# LightSensors_Buttons_LCD.net
KiCad netlist of a schematic drawn in Altium Designer
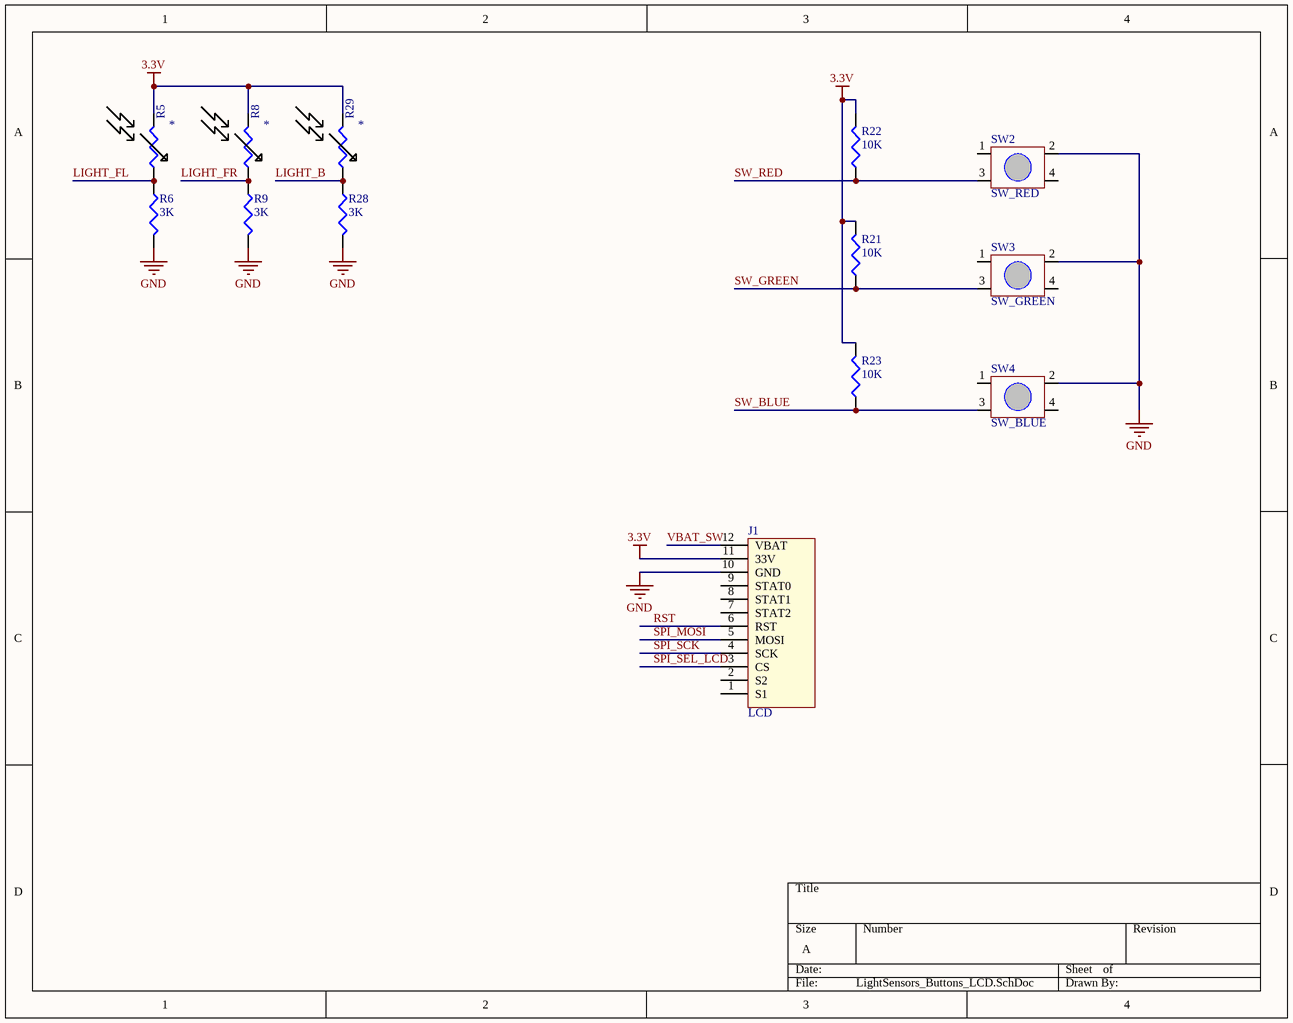
[diagram p0: LightSensors_Buttons_LCD.SchDoc]

(export (version "E")
  (design (tool "Eeschema 10.0.6"))
  (components
    (comp (ref "J1")
      (value "LCD")
      (footprint "LCD-6100breakout")
      (libsource (lib "mrone") (part "LCD-NokiaBreakout"))
    )
    (comp (ref "R5")
      (value "photoresistor")
      (footprint "photoresistor")
      (fields (field (name "ALTIUM_VALUE") "*"))
      (libsource (lib "mrone") (part "photoresistor"))
    )
    (comp (ref "R6")
      (value "3K")
      (footprint "RESC1608L")
      (description "Resistor")
      (fields (field (name "Comment") "Res3") (field (name "PUBLISHER") "Altium Limited"))
      (libsource (lib "Miscellaneous Devices") (part "Res3"))
    )
    (comp (ref "R8")
      (value "photoresistor")
      (footprint "photoresistor")
      (fields (field (name "ALTIUM_VALUE") "*"))
      (libsource (lib "mrone") (part "photoresistor"))
    )
    (comp (ref "R9")
      (value "3K")
      (footprint "RESC1608L")
      (description "Resistor")
      (fields (field (name "Comment") "Res3") (field (name "PUBLISHER") "Altium Limited"))
      (libsource (lib "Miscellaneous Devices") (part "Res3"))
    )
    (comp (ref "R21")
      (value "10K")
      (footprint "RESC1608L")
      (description "Resistor")
      (fields (field (name "Comment") "Res3") (field (name "PUBLISHER") "Altium Limited"))
      (libsource (lib "Miscellaneous Devices") (part "Res3"))
    )
    (comp (ref "R22")
      (value "10K")
      (footprint "RESC1608L")
      (description "Resistor")
      (fields (field (name "Comment") "Res3") (field (name "PUBLISHER") "Altium Limited"))
      (libsource (lib "Miscellaneous Devices") (part "Res3"))
    )
    (comp (ref "R23")
      (value "10K")
      (footprint "RESC1608L")
      (description "Resistor")
      (fields (field (name "Comment") "Res3") (field (name "PUBLISHER") "Altium Limited"))
      (libsource (lib "Miscellaneous Devices") (part "Res3"))
    )
    (comp (ref "R28")
      (value "3K")
      (footprint "RESC1608L")
      (description "Resistor")
      (fields (field (name "Comment") "Res3") (field (name "PUBLISHER") "Altium Limited"))
      (libsource (lib "Miscellaneous Devices") (part "Res3"))
    )
    (comp (ref "R29")
      (value "photoresistor")
      (footprint "photoresistor")
      (fields (field (name "ALTIUM_VALUE") "*"))
      (libsource (lib "mrone") (part "photoresistor"))
    )
    (comp (ref "SW2")
      (value "SW_RED")
      (footprint "SwitchTall-TL330")
      (libsource (lib "mrone") (part "Switch-TL330"))
    )
    (comp (ref "SW3")
      (value "SW_GREEN")
      (footprint "SwitchTall-TL330")
      (libsource (lib "mrone") (part "Switch-TL330"))
    )
    (comp (ref "SW4")
      (value "SW_BLUE")
      (footprint "SwitchTall-TL330")
      (libsource (lib "mrone") (part "Switch-TL330"))
    )
  )
  (nets
    (net (code "1") (name "/LIGHT_B") (class "Default")
      (node (ref "R28") (pin "1") (pinfunction "1_1") (pintype "passive"))
      (node (ref "R29") (pin "1") (pinfunction "1_1") (pintype "passive"))
    )
    (net (code "2") (name "/LIGHT_FL") (class "Default")
      (node (ref "R5") (pin "1") (pinfunction "1_1") (pintype "passive"))
      (node (ref "R6") (pin "1") (pinfunction "1_1") (pintype "passive"))
    )
    (net (code "3") (name "/LIGHT_FR") (class "Default")
      (node (ref "R8") (pin "1") (pinfunction "1_1") (pintype "passive"))
      (node (ref "R9") (pin "1") (pinfunction "1_1") (pintype "passive"))
    )
    (net (code "4") (name "/RST") (class "Default")
      (node (ref "J1") (pin "6") (pinfunction "RST_6") (pintype "passive"))
    )
    (net (code "5") (name "/SPI_MOSI") (class "Default")
      (node (ref "J1") (pin "5") (pinfunction "MOSI_5") (pintype "passive"))
    )
    (net (code "6") (name "/SPI_SCK") (class "Default")
      (node (ref "J1") (pin "4") (pinfunction "SCK_4") (pintype "passive"))
    )
    (net (code "7") (name "/SPI_SEL_LCD") (class "Default")
      (node (ref "J1") (pin "3") (pinfunction "CS_3") (pintype "passive"))
    )
    (net (code "8") (name "/SW_BLUE") (class "Default")
      (node (ref "R23") (pin "1") (pinfunction "1_1") (pintype "passive"))
      (node (ref "SW4") (pin "3") (pinfunction "3_3") (pintype "passive"))
    )
    (net (code "9") (name "/SW_GREEN") (class "Default")
      (node (ref "R21") (pin "1") (pinfunction "1_1") (pintype "passive"))
      (node (ref "SW3") (pin "3") (pinfunction "3_3") (pintype "passive"))
    )
    (net (code "10") (name "/SW_RED") (class "Default")
      (node (ref "R22") (pin "1") (pinfunction "1_1") (pintype "passive"))
      (node (ref "SW2") (pin "3") (pinfunction "3_3") (pintype "passive"))
    )
    (net (code "11") (name "/VBAT_SW") (class "Default")
      (node (ref "J1") (pin "12") (pinfunction "VBAT_12") (pintype "passive"))
    )
    (net (code "12") (name "3.3V") (class "Default")
      (node (ref "J1") (pin "11") (pinfunction "33V_11") (pintype "passive"))
      (node (ref "R21") (pin "2") (pinfunction "2_2") (pintype "passive"))
      (node (ref "R22") (pin "2") (pinfunction "2_2") (pintype "passive"))
      (node (ref "R23") (pin "2") (pinfunction "2_2") (pintype "passive"))
      (node (ref "R29") (pin "2") (pinfunction "2_2") (pintype "passive"))
      (node (ref "R5") (pin "2") (pinfunction "2_2") (pintype "passive"))
      (node (ref "R8") (pin "2") (pinfunction "2_2") (pintype "passive"))
    )
    (net (code "13") (name "GND") (class "Default")
      (node (ref "J1") (pin "10") (pinfunction "GND_10") (pintype "passive"))
      (node (ref "R28") (pin "2") (pinfunction "2_2") (pintype "passive"))
      (node (ref "R6") (pin "2") (pinfunction "2_2") (pintype "passive"))
      (node (ref "R9") (pin "2") (pinfunction "2_2") (pintype "passive"))
      (node (ref "SW2") (pin "2") (pinfunction "2_2") (pintype "passive"))
      (node (ref "SW3") (pin "2") (pinfunction "2_2") (pintype "passive"))
      (node (ref "SW4") (pin "2") (pinfunction "2_2") (pintype "passive"))
    )
    (net (code "14") (name "unconnected-(J1-S1-Pad1)") (class "Default")
      (node (ref "J1") (pin "1") (pinfunction "S1_1") (pintype "passive"))
    )
    (net (code "15") (name "unconnected-(J1-S2-Pad2)") (class "Default")
      (node (ref "J1") (pin "2") (pinfunction "S2_2") (pintype "passive"))
    )
    (net (code "16") (name "unconnected-(J1-STAT0-Pad9)") (class "Default")
      (node (ref "J1") (pin "9") (pinfunction "STAT0_9") (pintype "passive"))
    )
    (net (code "17") (name "unconnected-(J1-STAT1-Pad8)") (class "Default")
      (node (ref "J1") (pin "8") (pinfunction "STAT1_8") (pintype "passive"))
    )
    (net (code "18") (name "unconnected-(J1-STAT2-Pad7)") (class "Default")
      (node (ref "J1") (pin "7") (pinfunction "STAT2_7") (pintype "passive"))
    )
    (net (code "19") (name "unconnected-(SW2-Pad1)") (class "Default")
      (node (ref "SW2") (pin "1") (pinfunction "1_1") (pintype "passive"))
    )
    (net (code "20") (name "unconnected-(SW2-Pad4)") (class "Default")
      (node (ref "SW2") (pin "4") (pinfunction "4_4") (pintype "passive"))
    )
    (net (code "21") (name "unconnected-(SW3-Pad1)") (class "Default")
      (node (ref "SW3") (pin "1") (pinfunction "1_1") (pintype "passive"))
    )
    (net (code "22") (name "unconnected-(SW3-Pad4)") (class "Default")
      (node (ref "SW3") (pin "4") (pinfunction "4_4") (pintype "passive"))
    )
    (net (code "23") (name "unconnected-(SW4-Pad1)") (class "Default")
      (node (ref "SW4") (pin "1") (pinfunction "1_1") (pintype "passive"))
    )
    (net (code "24") (name "unconnected-(SW4-Pad4)") (class "Default")
      (node (ref "SW4") (pin "4") (pinfunction "4_4") (pintype "passive"))
    )
  )
)
